# SCH_Nfc-card-cameron_2024-10-10.net
KiCad netlist of a schematic drawn in EasyEDA
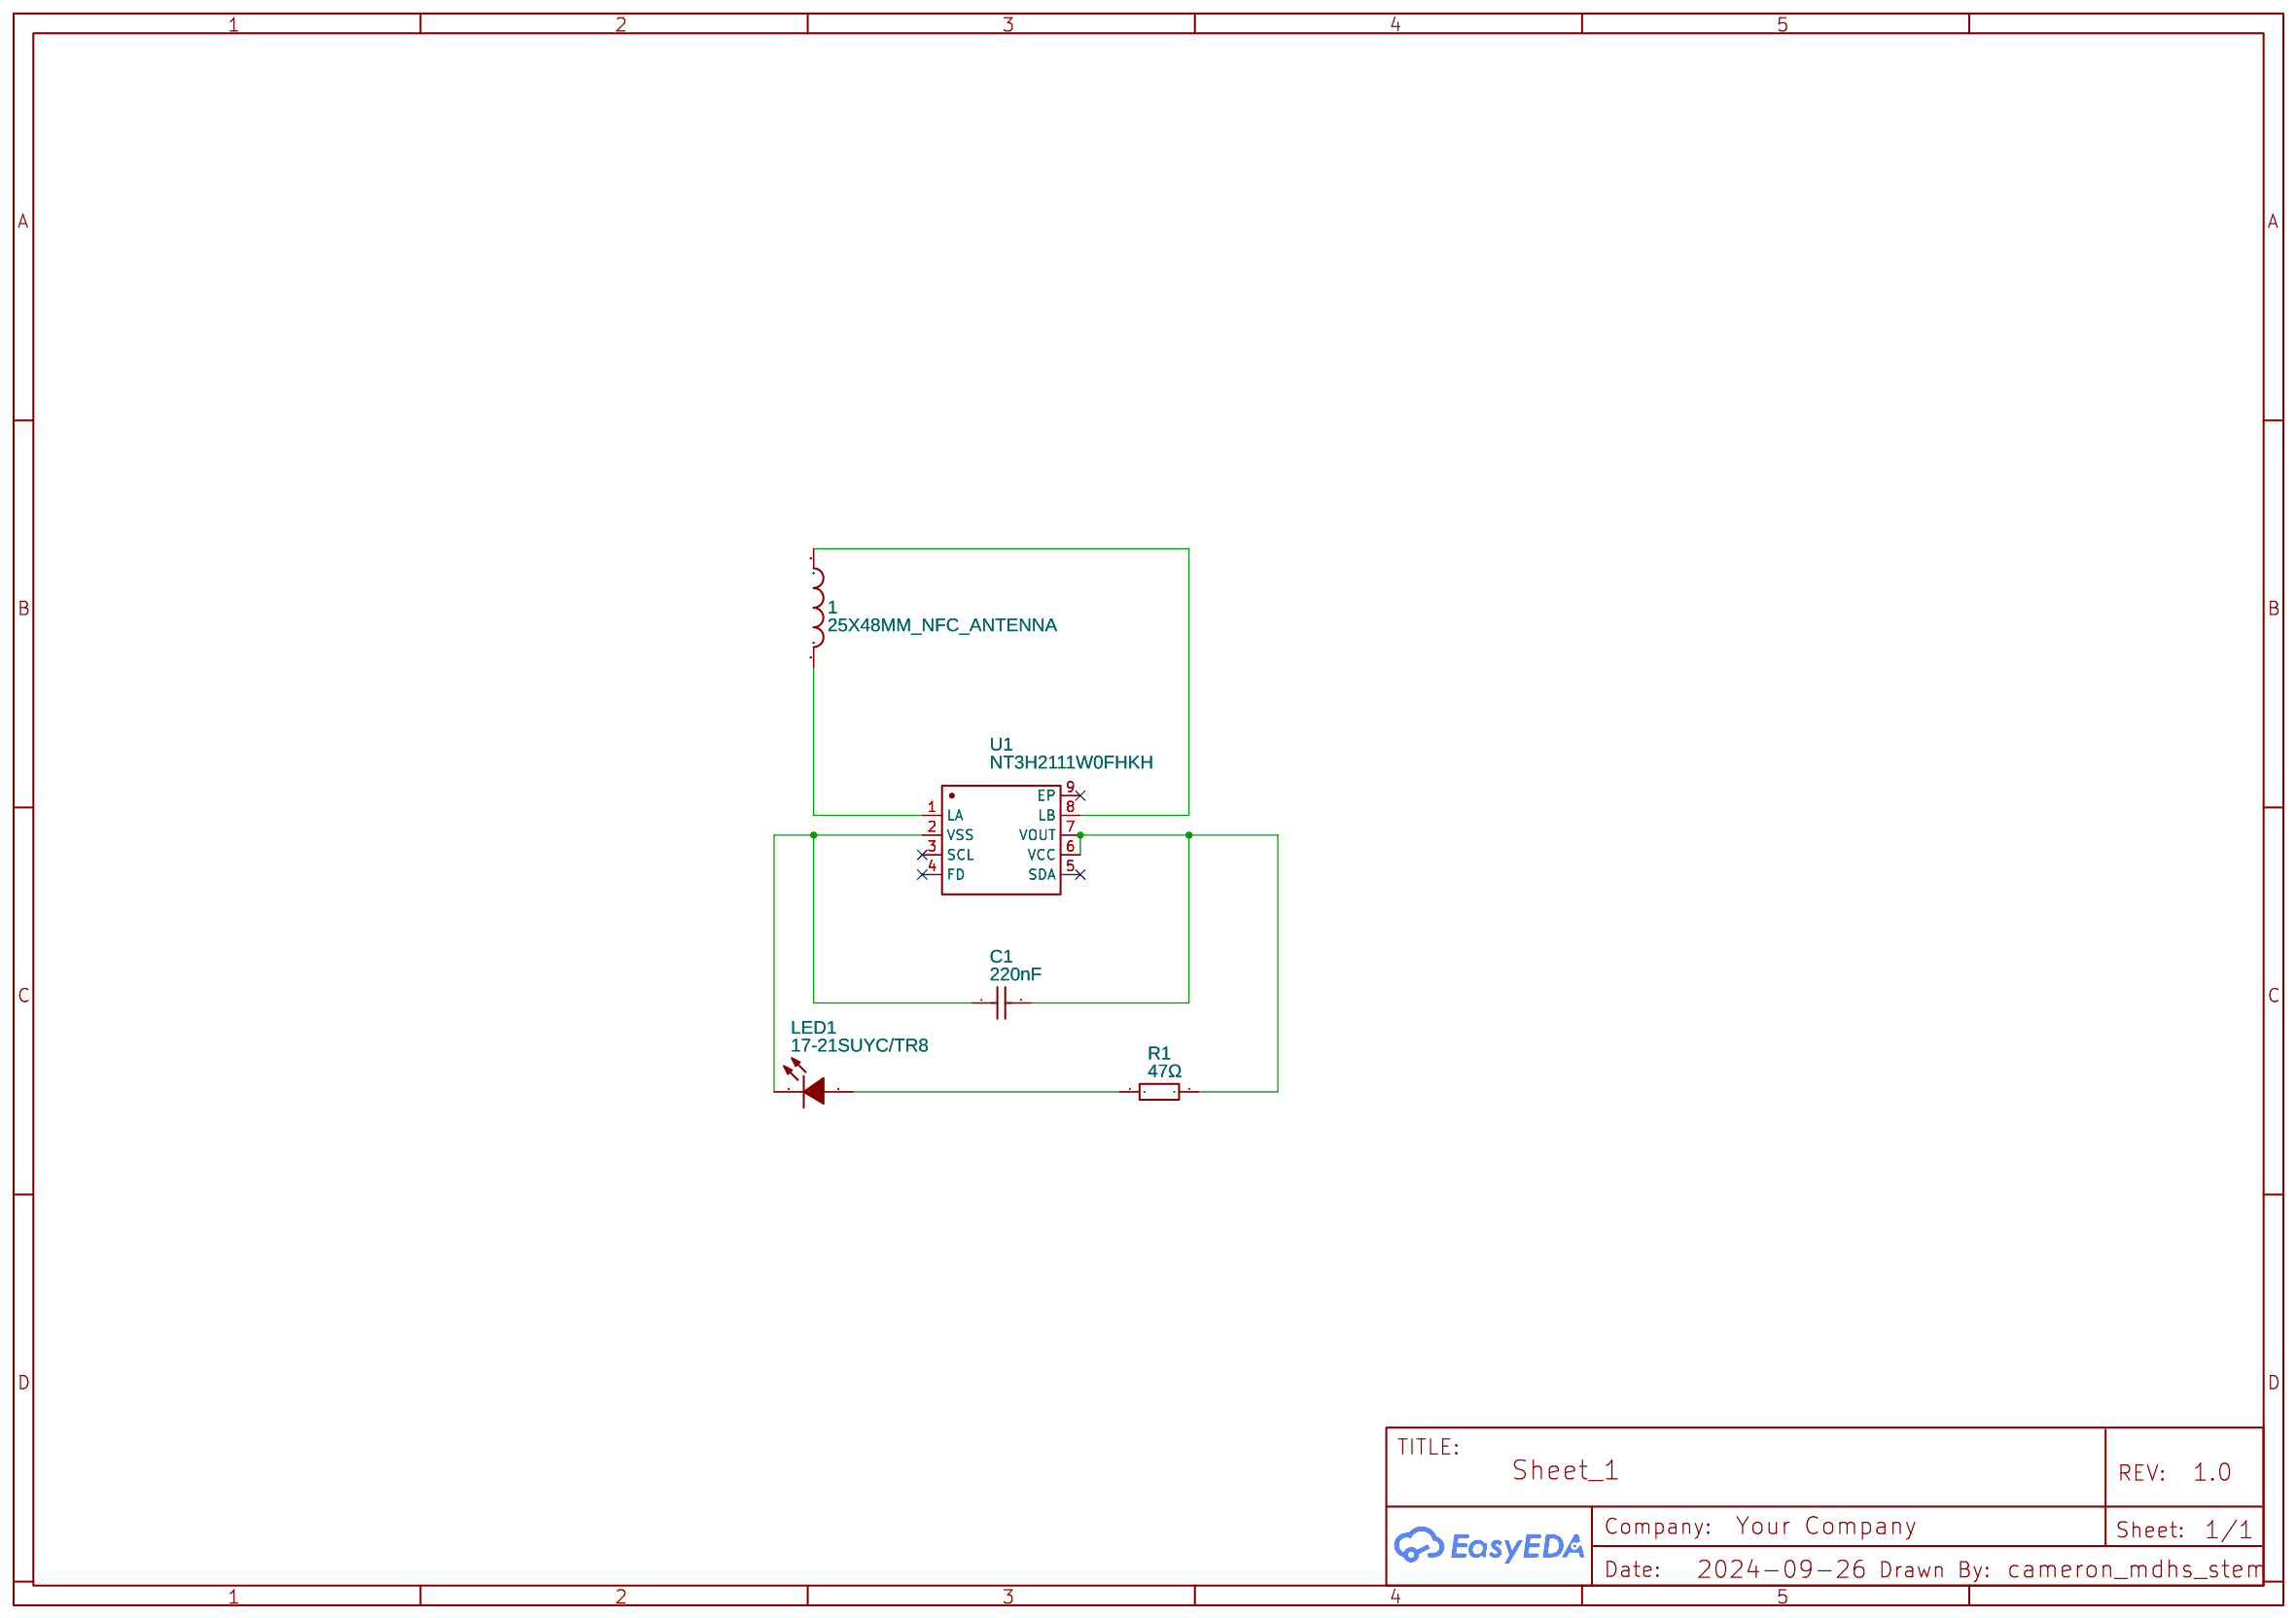
[diagram p0: schematic sheet]

(export (version "E")
  (design (tool "Eeschema 10.0.6"))
  (components
    (comp (ref "1") (value "25X48MM_NFC_ANTENNA") (libsource (lib "") (part "25X48MM_NFC_ANTENNA")))
    (comp (ref "C1")
      (value "220nF")
      (fields
        (field (name "Manufacturer Part") "CL10B224KA8NNNC")
        (field (name "Manufacturer") "SAMSUNG(三星)")
      )
      (libsource (lib "") (part "CL10B224KA8NNNC"))
    )
    (comp (ref "LED1")
      (value "17-21SUYC/TR8")
      (fields (field (name "Manufacturer Part") "KT-0805黄灯") (field (name "Manufacturer") "KENTO"))
      (libsource (lib "") (part "17-21SUYC/TR8"))
    )
    (comp (ref "R1")
      (value "47Ω")
      (fields
        (field (name "Manufacturer Part") "0603WAF470JT5E")
        (field (name "Manufacturer") "UNI-ROYAL(厚声)")
      )
      (libsource (lib "") (part "0603WAF470JT5E"))
    )
    (comp (ref "U1")
      (value "NT3H2111W0FHKH")
      (fields (field (name "Manufacturer") "NXP(恩智浦)"))
      (libsource (lib "") (part "NT3H2111W0FHKH"))
    )
  )
  (nets
    (net (code "1") (name "Net-(LED1-+)") (class "Default")
      (node (ref "LED1") (pin "1") (pinfunction "+_1") (pintype "unspecified"))
      (node (ref "R1") (pin "1") (pinfunction "1_1") (pintype "input"))
    )
    (net (code "2") (name "Net-(LED1--)") (class "Default")
      (node (ref "C1") (pin "1") (pinfunction "1_1") (pintype "input"))
      (node (ref "LED1") (pin "2") (pinfunction "-_2") (pintype "unspecified"))
      (node (ref "U1") (pin "2") (pinfunction "VSS_2") (pintype "unspecified"))
    )
    (net (code "3") (name "Net-(U1-LA)") (class "Default")
      (node (ref "1") (pin "P$2") (pinfunction "P$2_P$2") (pintype "bidirectional"))
      (node (ref "U1") (pin "1") (pinfunction "LA_1") (pintype "unspecified"))
    )
    (net (code "4") (name "Net-(U1-LB)") (class "Default")
      (node (ref "1") (pin "P$1") (pinfunction "P$1_P$1") (pintype "bidirectional"))
      (node (ref "U1") (pin "8") (pinfunction "LB_8") (pintype "unspecified"))
    )
    (net (code "5") (name "Net-(U1-VCC)") (class "Default")
      (node (ref "C1") (pin "2") (pinfunction "2_2") (pintype "input"))
      (node (ref "R1") (pin "2") (pinfunction "2_2") (pintype "input"))
      (node (ref "U1") (pin "6") (pinfunction "VCC_6") (pintype "unspecified"))
      (node (ref "U1") (pin "7") (pinfunction "VOUT_7") (pintype "unspecified"))
    )
    (net (code "6") (name "unconnected-(U1-EP-Pad9)") (class "Default")
      (node (ref "U1") (pin "9") (pinfunction "EP_9") (pintype "unspecified+no_connect"))
    )
    (net (code "7") (name "unconnected-(U1-FD-Pad4)") (class "Default")
      (node (ref "U1") (pin "4") (pinfunction "FD_4") (pintype "unspecified+no_connect"))
    )
    (net (code "8") (name "unconnected-(U1-SCL-Pad3)") (class "Default")
      (node (ref "U1") (pin "3") (pinfunction "SCL_3") (pintype "unspecified+no_connect"))
    )
    (net (code "9") (name "unconnected-(U1-SDA-Pad5)") (class "Default")
      (node (ref "U1") (pin "5") (pinfunction "SDA_5") (pintype "unspecified+no_connect"))
    )
  )
)
